# co2-sensor.net
KiCad netlist of a schematic drawn in EAGLE
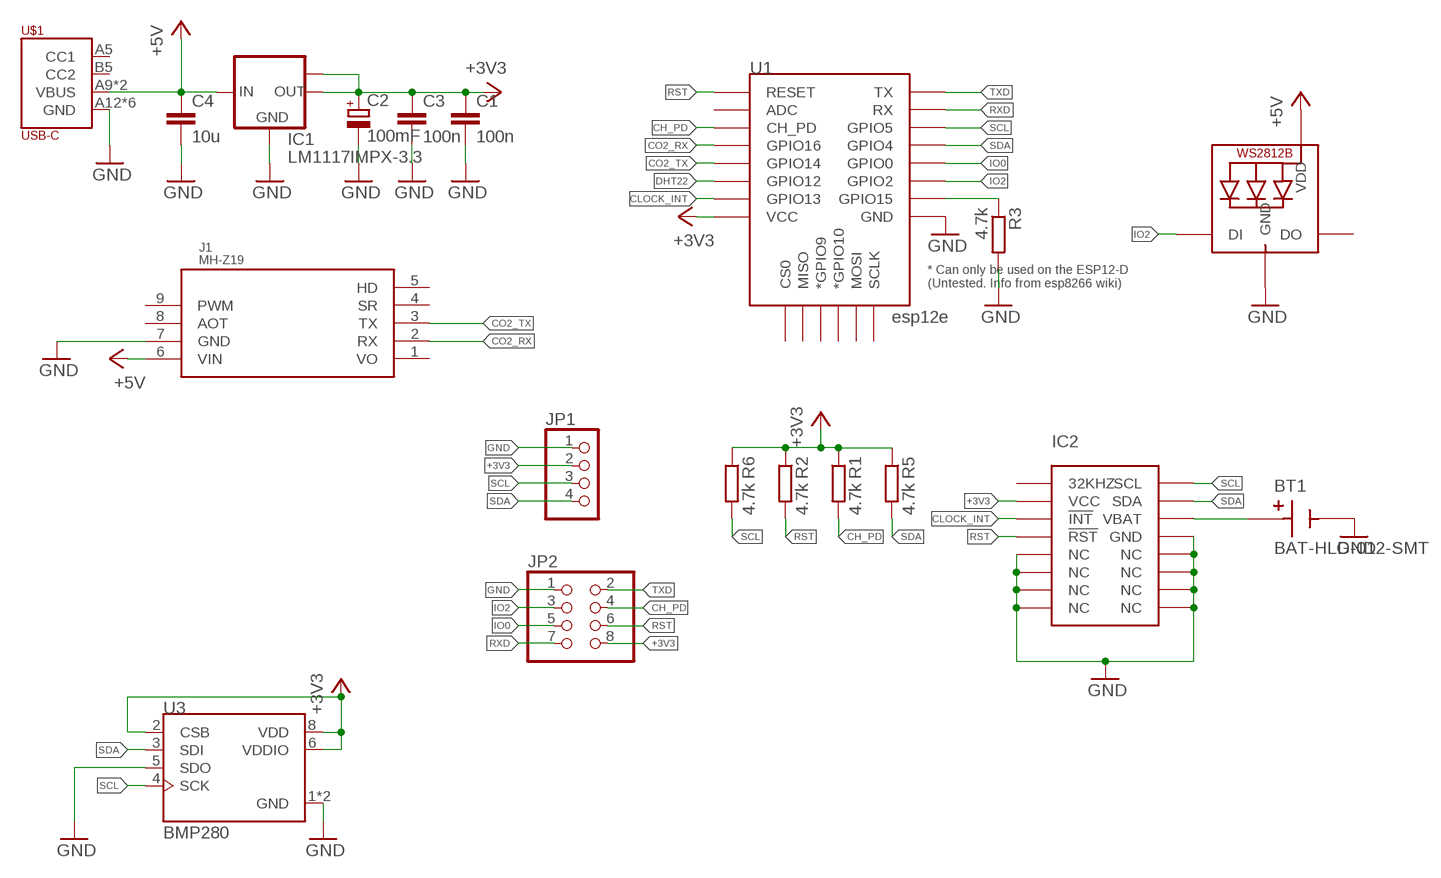
[diagram p0: schematic, sheet 1]

(export (version "E")
  (design (tool "Eeschema 10.0.6"))
  (components
    (comp (ref "BT1")
      (value "BAT-HLD-012-SMT")
      (footprint "eagle-import:BAT_BAT-HLD-012-SMT")
      (fields (field (name "MF") "Linx Technologies"))
      (libsource (lib "eagle-import") (part "BAT-HLD-012-SMT"))
    )
    (comp (ref "C1")
      (value "100n")
      (footprint "eagle-import:C0805")
      (libsource (lib "eagle-import") (part "C-EUC0805"))
    )
    (comp (ref "C2")
      (value "100mF")
      (footprint "eagle-import:CT3216")
      (libsource (lib "eagle-import") (part "CPOL-EUCT3216"))
    )
    (comp (ref "C3")
      (value "100n")
      (footprint "eagle-import:C0805")
      (libsource (lib "eagle-import") (part "C-EUC0805"))
    )
    (comp (ref "C4")
      (value "10u")
      (footprint "eagle-import:C0805")
      (libsource (lib "eagle-import") (part "C-EUC0805"))
    )
    (comp (ref "IC1")
      (value "LM1117IMPX-3.3")
      (footprint "eagle-import:SOT223")
      (libsource (lib "eagle-import") (part "LM1117IMPX-3.3"))
    )
    (comp (ref "IC2")
      (value "DS3231SOIC-16W")
      (footprint "eagle-import:SOIC-16W")
      (libsource (lib "eagle-import") (part "DS3231SOIC-16W"))
    )
    (comp (ref "J1")
      (value "MH-Z19")
      (footprint "eagle-import:MH-Z19-REV")
      (libsource (lib "eagle-import") (part "MH-Z19"))
    )
    (comp (ref "JP1")
      (value "PINHD-1X4")
      (footprint "eagle-import:1X04")
      (libsource (lib "eagle-import") (part "PINHD-1X4"))
    )
    (comp (ref "JP2")
      (value "PINHD-2X4")
      (footprint "eagle-import:2X04")
      (libsource (lib "eagle-import") (part "PINHD-2X4"))
    )
    (comp (ref "LED1")
      (value "WS2812B5050")
      (footprint "eagle-import:WS2812B")
      (fields (field (name "MF") "Worldsemi") (field (name "MP") "WS2812B"))
      (libsource (lib "eagle-import") (part "WS2812B5050"))
    )
    (comp (ref "R1")
      (value "4.7k")
      (footprint "eagle-import:M0805")
      (libsource (lib "eagle-import") (part "R-EU_M0805"))
    )
    (comp (ref "R2")
      (value "4.7k")
      (footprint "eagle-import:M0805")
      (libsource (lib "eagle-import") (part "R-EU_M0805"))
    )
    (comp (ref "R3")
      (value "4.7k")
      (footprint "eagle-import:M0805")
      (libsource (lib "eagle-import") (part "R-EU_M0805"))
    )
    (comp (ref "R5")
      (value "4.7k")
      (footprint "eagle-import:M0805")
      (libsource (lib "eagle-import") (part "R-EU_M0805"))
    )
    (comp (ref "R6")
      (value "4.7k")
      (footprint "eagle-import:M0805")
      (libsource (lib "eagle-import") (part "R-EU_M0805"))
    )
    (comp (ref "U$1")
      (value "USB-C")
      (footprint "eagle-import:USB-C")
      (libsource (lib "eagle-import") (part "USB-C"))
    )
    (comp (ref "U1")
      (value "esp12e")
      (footprint "eagle-import:ESP12E-SMD")
      (libsource (lib "eagle-import") (part "ESP12ESMD"))
    )
    (comp (ref "U3")
      (value "BMP280")
      (footprint "eagle-import:XDCR_BMP280")
      (fields (field (name "MF") "Bosch"))
      (libsource (lib "eagle-import") (part "BMP280"))
    )
  )
  (nets
    (net (code "1") (name "+3V3") (class "Default")
      (node (ref "C1") (pin "1") (pinfunction "1_1") (pintype "passive"))
      (node (ref "C2") (pin "+") (pinfunction "+_+") (pintype "passive"))
      (node (ref "C3") (pin "1") (pinfunction "1_1") (pintype "passive"))
      (node (ref "IC1") (pin "2") (pinfunction "OUT_2") (pintype "passive"))
      (node (ref "IC1") (pin "TAB") (pinfunction "OUT1_TAB") (pintype "passive"))
      (node (ref "IC2") (pin "2") (pinfunction "VCC_2") (pintype "bidirectional"))
      (node (ref "JP1") (pin "2") (pinfunction "2_2") (pintype "passive"))
      (node (ref "JP2") (pin "8") (pinfunction "8_8") (pintype "passive"))
      (node (ref "R1") (pin "1") (pinfunction "1_1") (pintype "passive"))
      (node (ref "R2") (pin "1") (pinfunction "1_1") (pintype "passive"))
      (node (ref "R5") (pin "1") (pinfunction "1_1") (pintype "passive"))
      (node (ref "R6") (pin "1") (pinfunction "1_1") (pintype "passive"))
      (node (ref "U1") (pin "VCC") (pinfunction "VCC_VCC") (pintype "bidirectional"))
      (node (ref "U3") (pin "2") (pinfunction "CSB_2") (pintype "input"))
      (node (ref "U3") (pin "6") (pinfunction "VDDIO_6") (pintype "power_in"))
      (node (ref "U3") (pin "8") (pinfunction "VDD_8") (pintype "power_in"))
    )
    (net (code "2") (name "+5V") (class "Default")
      (node (ref "C4") (pin "1") (pinfunction "1_1") (pintype "passive"))
      (node (ref "IC1") (pin "3") (pinfunction "IN_3") (pintype "input"))
      (node (ref "J1") (pin "6") (pinfunction "VIN_6") (pintype "power_in"))
      (node (ref "LED1") (pin "1-VDD") (pinfunction "VDD_1-VDD") (pintype "power_in"))
      (node (ref "U$1") (pin "A9") (pinfunction "VBUS_A9") (pintype "power_in"))
      (node (ref "U$1") (pin "B9") (pinfunction "VBUS_B9") (pintype "power_in"))
    )
    (net (code "3") (name "/VO") (class "Default")
      (node (ref "J1") (pin "1") (pinfunction "VO_1") (pintype "power_in"))
    )
    (net (code "4") (name "CH_PD") (class "Default")
      (node (ref "JP2") (pin "4") (pinfunction "4_4") (pintype "passive"))
      (node (ref "R1") (pin "2") (pinfunction "2_2") (pintype "passive"))
      (node (ref "U1") (pin "CH_PD") (pinfunction "CH_PD_CH_PD") (pintype "bidirectional"))
    )
    (net (code "5") (name "CLOCK_INT") (class "Default")
      (node (ref "IC2") (pin "3") (pinfunction "~{INT}_3") (pintype "bidirectional"))
      (node (ref "U1") (pin "GPIO13") (pinfunction "GPIO13_GPIO13") (pintype "bidirectional"))
    )
    (net (code "6") (name "CO2_RX") (class "Default")
      (node (ref "J1") (pin "2") (pinfunction "RX_2") (pintype "input"))
      (node (ref "U1") (pin "GPIO16") (pinfunction "GPIO16_GPIO16") (pintype "bidirectional"))
    )
    (net (code "7") (name "CO2_TX") (class "Default")
      (node (ref "J1") (pin "3") (pinfunction "TX_3") (pintype "output"))
      (node (ref "U1") (pin "GPIO14") (pinfunction "GPIO14_GPIO14") (pintype "bidirectional"))
    )
    (net (code "8") (name "DHT22") (class "Default")
      (node (ref "U1") (pin "GPIO12") (pinfunction "GPIO12_GPIO12") (pintype "bidirectional"))
    )
    (net (code "9") (name "GND") (class "Default")
      (node (ref "BT1") (pin "N") (pinfunction "N_N") (pintype "passive"))
      (node (ref "C1") (pin "2") (pinfunction "2_2") (pintype "passive"))
      (node (ref "C2") (pin "-") (pinfunction "-_-") (pintype "passive"))
      (node (ref "C3") (pin "2") (pinfunction "2_2") (pintype "passive"))
      (node (ref "C4") (pin "2") (pinfunction "2_2") (pintype "passive"))
      (node (ref "IC1") (pin "1") (pinfunction "GND_1") (pintype "input"))
      (node (ref "IC2") (pin "10") (pinfunction "NC_10") (pintype "bidirectional"))
      (node (ref "IC2") (pin "11") (pinfunction "NC_11") (pintype "bidirectional"))
      (node (ref "IC2") (pin "12") (pinfunction "NC_12") (pintype "bidirectional"))
      (node (ref "IC2") (pin "13") (pinfunction "GND_13") (pintype "bidirectional"))
      (node (ref "IC2") (pin "5") (pinfunction "NC_5") (pintype "bidirectional"))
      (node (ref "IC2") (pin "6") (pinfunction "NC_6") (pintype "bidirectional"))
      (node (ref "IC2") (pin "7") (pinfunction "NC_7") (pintype "bidirectional"))
      (node (ref "IC2") (pin "8") (pinfunction "NC_8") (pintype "bidirectional"))
      (node (ref "IC2") (pin "9") (pinfunction "NC_9") (pintype "bidirectional"))
      (node (ref "J1") (pin "7") (pinfunction "GND_7") (pintype "power_in"))
      (node (ref "JP1") (pin "1") (pinfunction "1_1") (pintype "passive"))
      (node (ref "JP2") (pin "1") (pinfunction "1_1") (pintype "passive"))
      (node (ref "LED1") (pin "3-GND") (pinfunction "GND_3-GND") (pintype "power_in"))
      (node (ref "R3") (pin "2") (pinfunction "2_2") (pintype "passive"))
      (node (ref "U$1") (pin "A12") (pinfunction "GND_A12") (pintype "power_in"))
      (node (ref "U$1") (pin "B12") (pinfunction "GND_B12") (pintype "power_in"))
      (node (ref "U$1") (pin "P$10") (pinfunction "GND_P$10") (pintype "power_in"))
      (node (ref "U$1") (pin "P$7") (pinfunction "GND_P$7") (pintype "power_in"))
      (node (ref "U$1") (pin "P$8") (pinfunction "GND_P$8") (pintype "power_in"))
      (node (ref "U$1") (pin "P$9") (pinfunction "GND_P$9") (pintype "power_in"))
      (node (ref "U1") (pin "GND") (pinfunction "GND_GND") (pintype "bidirectional"))
      (node (ref "U3") (pin "1") (pinfunction "GND_1") (pintype "power_in"))
      (node (ref "U3") (pin "5") (pinfunction "SDO_5") (pintype "bidirectional"))
      (node (ref "U3") (pin "7") (pinfunction "GND_7") (pintype "power_in"))
    )
    (net (code "10") (name "IO0") (class "Default")
      (node (ref "JP2") (pin "5") (pinfunction "5_5") (pintype "passive"))
      (node (ref "U1") (pin "GPIO0") (pinfunction "GPIO0_GPIO0") (pintype "bidirectional"))
    )
    (net (code "11") (name "IO2") (class "Default")
      (node (ref "JP2") (pin "3") (pinfunction "3_3") (pintype "passive"))
      (node (ref "LED1") (pin "4-DIN") (pinfunction "DI_4-DIN") (pintype "input"))
      (node (ref "U1") (pin "GPIO2") (pinfunction "GPIO2_GPIO2") (pintype "bidirectional"))
    )
    (net (code "12") (name "Net-(IC2-VBAT)") (class "Default")
      (node (ref "BT1") (pin "P1") (pinfunction "P_P1") (pintype "passive"))
      (node (ref "BT1") (pin "P2") (pinfunction "P_P2") (pintype "passive"))
      (node (ref "IC2") (pin "14") (pinfunction "VBAT_14") (pintype "bidirectional"))
    )
    (net (code "13") (name "Net-(R3-Pad1)") (class "Default")
      (node (ref "R3") (pin "1") (pinfunction "1_1") (pintype "passive"))
      (node (ref "U1") (pin "GPIO15") (pinfunction "GPIO15_GPIO15") (pintype "bidirectional"))
    )
    (net (code "14") (name "RST") (class "Default")
      (node (ref "IC2") (pin "4") (pinfunction "~{RST}_4") (pintype "bidirectional"))
      (node (ref "JP2") (pin "6") (pinfunction "6_6") (pintype "passive"))
      (node (ref "R2") (pin "2") (pinfunction "2_2") (pintype "passive"))
      (node (ref "U1") (pin "RESET") (pinfunction "RESET_RESET") (pintype "bidirectional"))
    )
    (net (code "15") (name "RXD") (class "Default")
      (node (ref "JP2") (pin "7") (pinfunction "7_7") (pintype "passive"))
      (node (ref "U1") (pin "RXD0") (pinfunction "RX_RXD0") (pintype "bidirectional"))
    )
    (net (code "16") (name "SCL") (class "Default")
      (node (ref "IC2") (pin "16") (pinfunction "SCL_16") (pintype "bidirectional"))
      (node (ref "JP1") (pin "3") (pinfunction "3_3") (pintype "passive"))
      (node (ref "R6") (pin "2") (pinfunction "2_2") (pintype "passive"))
      (node (ref "U1") (pin "GPIO5") (pinfunction "GPIO5_GPIO5") (pintype "bidirectional"))
      (node (ref "U3") (pin "4") (pinfunction "SCK_4") (pintype "input"))
    )
    (net (code "17") (name "SDA") (class "Default")
      (node (ref "IC2") (pin "15") (pinfunction "SDA_15") (pintype "bidirectional"))
      (node (ref "JP1") (pin "4") (pinfunction "4_4") (pintype "passive"))
      (node (ref "R5") (pin "2") (pinfunction "2_2") (pintype "passive"))
      (node (ref "U1") (pin "GPIO4") (pinfunction "GPIO4_GPIO4") (pintype "bidirectional"))
      (node (ref "U3") (pin "3") (pinfunction "SDI_3") (pintype "bidirectional"))
    )
    (net (code "18") (name "TXD") (class "Default")
      (node (ref "JP2") (pin "2") (pinfunction "2_2") (pintype "passive"))
      (node (ref "U1") (pin "TXD0") (pinfunction "TX_TXD0") (pintype "bidirectional"))
    )
    (net (code "19") (name "unconnected-(IC2-32KHZ-Pad1)") (class "Default")
      (node (ref "IC2") (pin "1") (pinfunction "32KHZ_1") (pintype "bidirectional"))
    )
    (net (code "20") (name "unconnected-(J1-AOT-Pad8)") (class "Default")
      (node (ref "J1") (pin "8") (pinfunction "AOT_8") (pintype "no_connect"))
    )
    (net (code "21") (name "unconnected-(J1-HD-Pad5)") (class "Default")
      (node (ref "J1") (pin "5") (pinfunction "HD_5") (pintype "input"))
    )
    (net (code "22") (name "unconnected-(J1-PWM-Pad9)") (class "Default")
      (node (ref "J1") (pin "9") (pinfunction "PWM_9") (pintype "output"))
    )
    (net (code "23") (name "unconnected-(J1-SR-Pad4)") (class "Default")
      (node (ref "J1") (pin "4") (pinfunction "SR_4") (pintype "no_connect"))
    )
    (net (code "24") (name "unconnected-(LED1-DO-Pad2-DOUT)") (class "Default")
      (node (ref "LED1") (pin "2-DOUT") (pinfunction "DO_2-DOUT") (pintype "output"))
    )
    (net (code "25") (name "unconnected-(U$1-CC1-PadA5)") (class "Default")
      (node (ref "U$1") (pin "A5") (pinfunction "CC1_A5") (pintype "bidirectional"))
    )
    (net (code "26") (name "unconnected-(U$1-CC2-PadB5)") (class "Default")
      (node (ref "U$1") (pin "B5") (pinfunction "CC2_B5") (pintype "bidirectional"))
    )
    (net (code "27") (name "unconnected-(U1-*GPIO9-PadGPIO9)") (class "Default")
      (node (ref "U1") (pin "GPIO9") (pinfunction "*GPIO9_GPIO9") (pintype "bidirectional"))
    )
    (net (code "28") (name "unconnected-(U1-*GPIO10-PadGPIO10)") (class "Default")
      (node (ref "U1") (pin "GPIO10") (pinfunction "*GPIO10_GPIO10") (pintype "bidirectional"))
    )
    (net (code "29") (name "unconnected-(U1-PadADC)") (class "Default")
      (node (ref "U1") (pin "ADC") (pinfunction "ADC_ADC") (pintype "bidirectional"))
    )
    (net (code "30") (name "unconnected-(U1-PadCS0)") (class "Default")
      (node (ref "U1") (pin "CS0") (pinfunction "CS0_CS0") (pintype "bidirectional"))
    )
    (net (code "31") (name "unconnected-(U1-PadMISO)") (class "Default")
      (node (ref "U1") (pin "MISO") (pinfunction "MISO_MISO") (pintype "bidirectional"))
    )
    (net (code "32") (name "unconnected-(U1-PadMOSI)") (class "Default")
      (node (ref "U1") (pin "MOSI") (pinfunction "MOSI_MOSI") (pintype "bidirectional"))
    )
    (net (code "33") (name "unconnected-(U1-PadSCLK)") (class "Default")
      (node (ref "U1") (pin "SCLK") (pinfunction "SCLK_SCLK") (pintype "bidirectional"))
    )
  )
)
